# EasterEgg.net
KiCad netlist of a schematic drawn in EAGLE
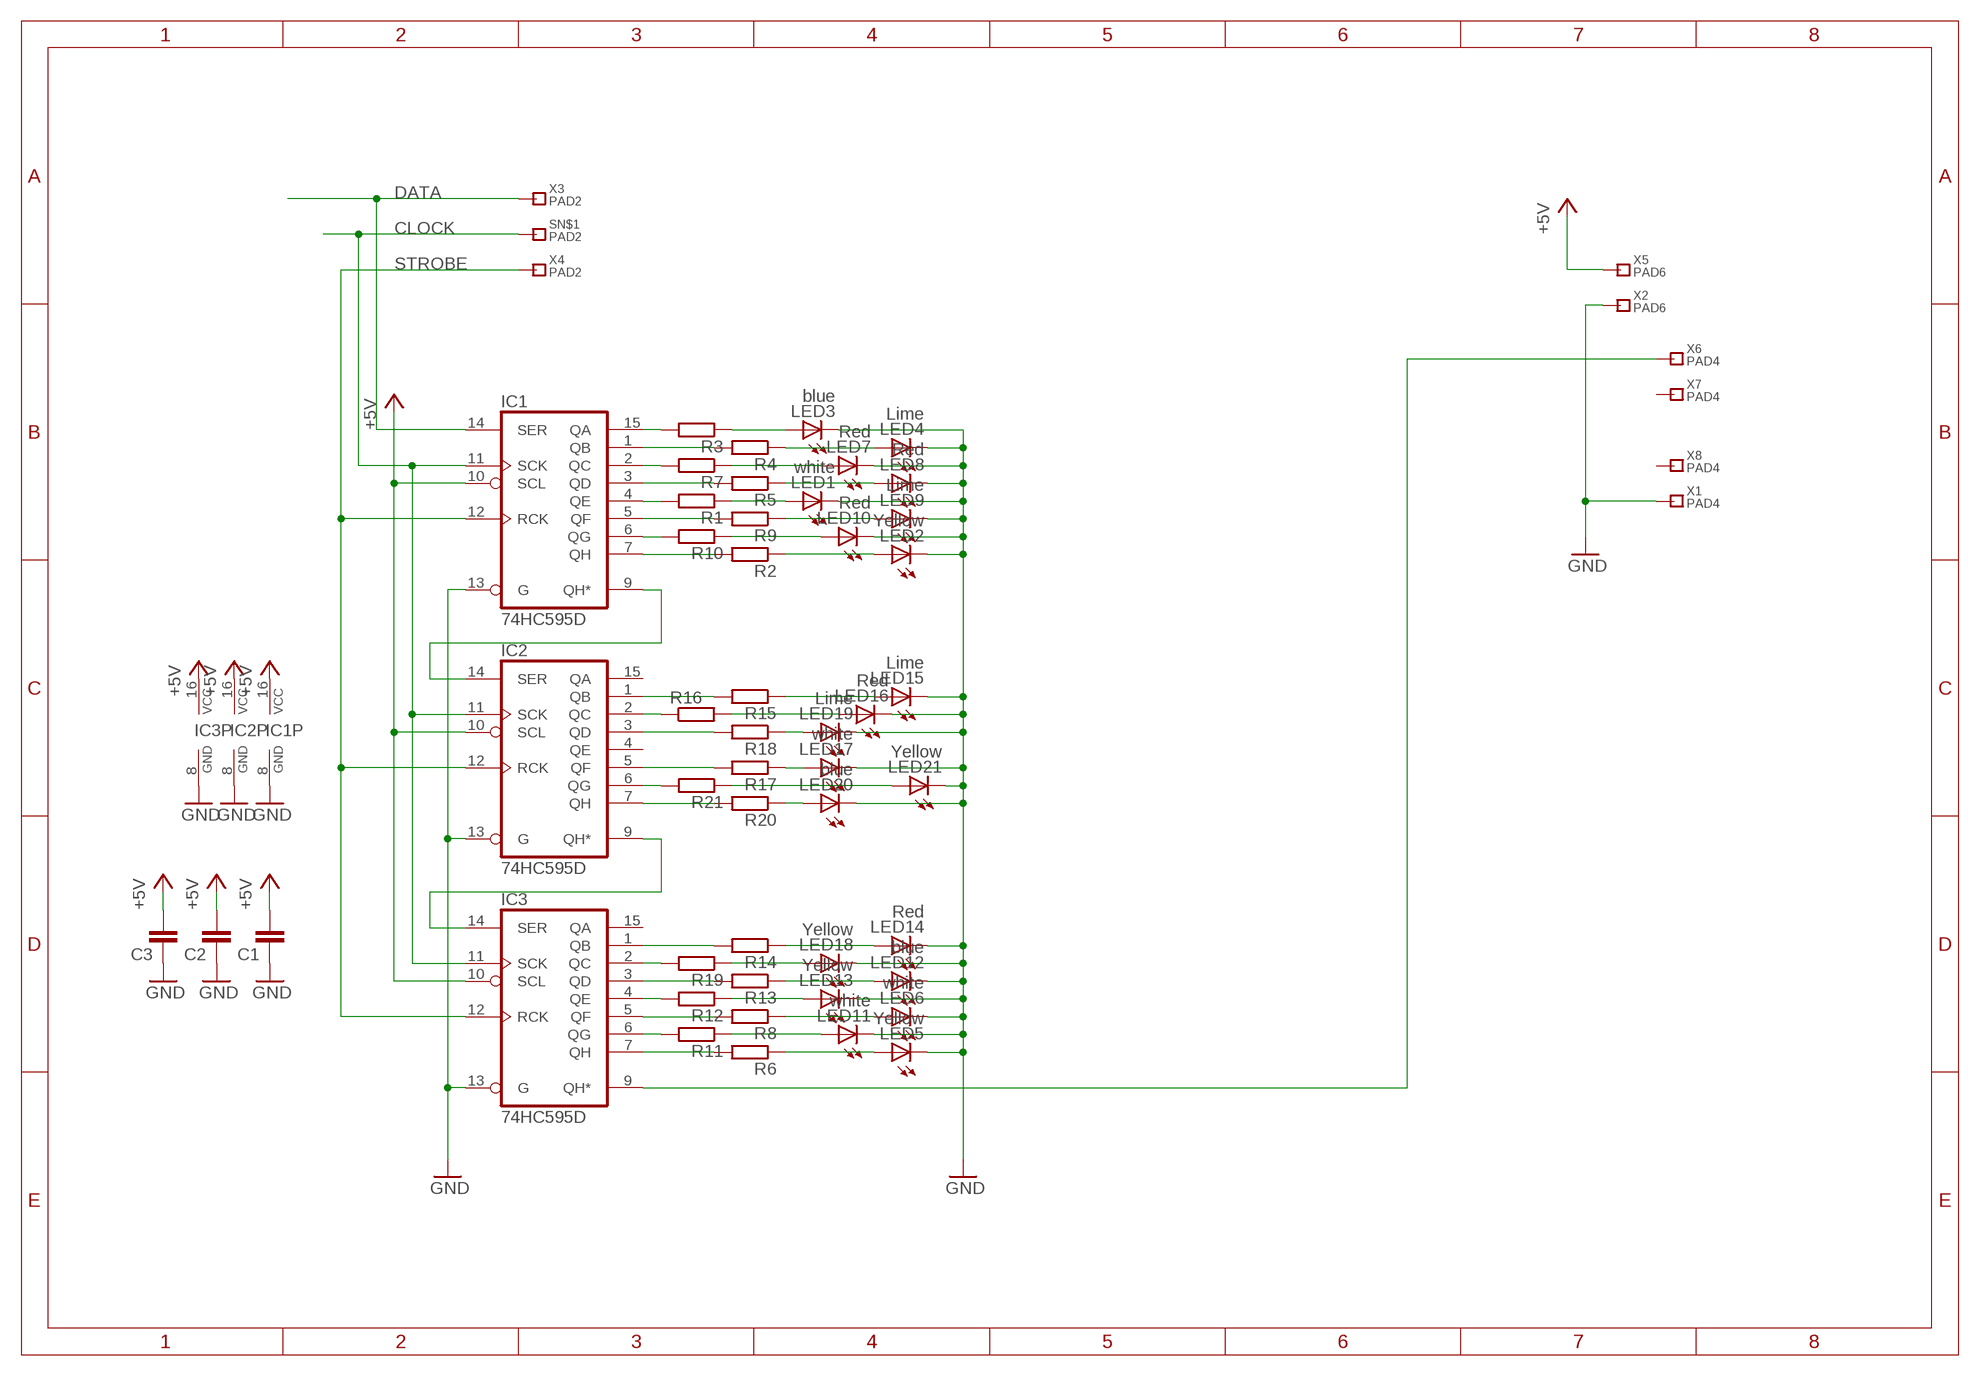
[diagram p0: schematic, sheet 1]

(export (version "E")
  (design (tool "Eeschema 10.0.6"))
  (components
    (comp (ref "C1")
      (value "C-EUC0805")
      (footprint "eagle-import:C0805")
      (libsource (lib "eagle-import") (part "C-EUC0805"))
    )
    (comp (ref "C2")
      (value "C-EUC0805")
      (footprint "eagle-import:C0805")
      (libsource (lib "eagle-import") (part "C-EUC0805"))
    )
    (comp (ref "C3")
      (value "C-EUC0805")
      (footprint "eagle-import:C0805")
      (libsource (lib "eagle-import") (part "C-EUC0805"))
    )
    (comp (ref "IC1")
      (value "74HC595D")
      (footprint "eagle-import:SO16")
      (libsource (lib "eagle-import") (part "74595DHC"))
    )
    (comp (ref "IC2")
      (value "74HC595D")
      (footprint "eagle-import:SO16")
      (libsource (lib "eagle-import") (part "74595DHC"))
    )
    (comp (ref "IC3")
      (value "74HC595D")
      (footprint "eagle-import:SO16")
      (libsource (lib "eagle-import") (part "74595DHC"))
    )
    (comp (ref "LED1")
      (value "white")
      (footprint "eagle-import:LED3MM")
      (libsource (lib "eagle-import") (part "LED3MM"))
    )
    (comp (ref "LED2")
      (value "Yellow")
      (footprint "eagle-import:LED3MM")
      (libsource (lib "eagle-import") (part "LED3MM"))
    )
    (comp (ref "LED3")
      (value "blue")
      (footprint "eagle-import:LED3MM")
      (libsource (lib "eagle-import") (part "LED3MM"))
    )
    (comp (ref "LED4")
      (value "Lime")
      (footprint "eagle-import:LED3MM")
      (libsource (lib "eagle-import") (part "LED3MM"))
    )
    (comp (ref "LED5")
      (value "Yellow")
      (footprint "eagle-import:LED3MM")
      (libsource (lib "eagle-import") (part "LED3MM"))
    )
    (comp (ref "LED6")
      (value "white")
      (footprint "eagle-import:LED3MM")
      (libsource (lib "eagle-import") (part "LED3MM"))
    )
    (comp (ref "LED7")
      (value "Red")
      (footprint "eagle-import:LED3MM")
      (libsource (lib "eagle-import") (part "LED3MM"))
    )
    (comp (ref "LED8")
      (value "Red")
      (footprint "eagle-import:LED3MM")
      (libsource (lib "eagle-import") (part "LED3MM"))
    )
    (comp (ref "LED9")
      (value "Lime")
      (footprint "eagle-import:LED3MM")
      (libsource (lib "eagle-import") (part "LED3MM"))
    )
    (comp (ref "LED10")
      (value "Red")
      (footprint "eagle-import:LED3MM")
      (libsource (lib "eagle-import") (part "LED3MM"))
    )
    (comp (ref "LED11")
      (value "white")
      (footprint "eagle-import:LED3MM")
      (libsource (lib "eagle-import") (part "LED3MM"))
    )
    (comp (ref "LED12")
      (value "blue")
      (footprint "eagle-import:LED3MM")
      (libsource (lib "eagle-import") (part "LED3MM"))
    )
    (comp (ref "LED13")
      (value "Yellow")
      (footprint "eagle-import:LED3MM")
      (libsource (lib "eagle-import") (part "LED3MM"))
    )
    (comp (ref "LED14")
      (value "Red")
      (footprint "eagle-import:LED3MM")
      (libsource (lib "eagle-import") (part "LED3MM"))
    )
    (comp (ref "LED15")
      (value "Lime")
      (footprint "eagle-import:LED3MM")
      (libsource (lib "eagle-import") (part "LED3MM"))
    )
    (comp (ref "LED16")
      (value "Red")
      (footprint "eagle-import:LED3MM")
      (libsource (lib "eagle-import") (part "LED3MM"))
    )
    (comp (ref "LED17")
      (value "white")
      (footprint "eagle-import:LED3MM")
      (libsource (lib "eagle-import") (part "LED3MM"))
    )
    (comp (ref "LED18")
      (value "Yellow")
      (footprint "eagle-import:LED3MM")
      (libsource (lib "eagle-import") (part "LED3MM"))
    )
    (comp (ref "LED19")
      (value "Lime")
      (footprint "eagle-import:LED3MM")
      (libsource (lib "eagle-import") (part "LED3MM"))
    )
    (comp (ref "LED20")
      (value "blue")
      (footprint "eagle-import:LED3MM")
      (libsource (lib "eagle-import") (part "LED3MM"))
    )
    (comp (ref "LED21")
      (value "Yellow")
      (footprint "eagle-import:LED3MM")
      (libsource (lib "eagle-import") (part "LED3MM"))
    )
    (comp (ref "R1")
      (value "R-EU_R1206")
      (footprint "eagle-import:R1206")
      (libsource (lib "eagle-import") (part "R-EU_R1206"))
    )
    (comp (ref "R2")
      (value "R-EU_R1206")
      (footprint "eagle-import:R1206")
      (libsource (lib "eagle-import") (part "R-EU_R1206"))
    )
    (comp (ref "R3")
      (value "R-EU_R1206")
      (footprint "eagle-import:R1206")
      (libsource (lib "eagle-import") (part "R-EU_R1206"))
    )
    (comp (ref "R4")
      (value "R-EU_R1206")
      (footprint "eagle-import:R1206")
      (libsource (lib "eagle-import") (part "R-EU_R1206"))
    )
    (comp (ref "R5")
      (value "R-EU_R1206")
      (footprint "eagle-import:R1206")
      (libsource (lib "eagle-import") (part "R-EU_R1206"))
    )
    (comp (ref "R6")
      (value "R-EU_R1206")
      (footprint "eagle-import:R1206")
      (libsource (lib "eagle-import") (part "R-EU_R1206"))
    )
    (comp (ref "R7")
      (value "R-EU_R1206")
      (footprint "eagle-import:R1206")
      (libsource (lib "eagle-import") (part "R-EU_R1206"))
    )
    (comp (ref "R8")
      (value "R-EU_R1206")
      (footprint "eagle-import:R1206")
      (libsource (lib "eagle-import") (part "R-EU_R1206"))
    )
    (comp (ref "R9")
      (value "R-EU_R1206")
      (footprint "eagle-import:R1206")
      (libsource (lib "eagle-import") (part "R-EU_R1206"))
    )
    (comp (ref "R10")
      (value "R-EU_R1206")
      (footprint "eagle-import:R1206")
      (libsource (lib "eagle-import") (part "R-EU_R1206"))
    )
    (comp (ref "R11")
      (value "R-EU_R1206")
      (footprint "eagle-import:R1206")
      (libsource (lib "eagle-import") (part "R-EU_R1206"))
    )
    (comp (ref "R12")
      (value "R-EU_R1206")
      (footprint "eagle-import:R1206")
      (libsource (lib "eagle-import") (part "R-EU_R1206"))
    )
    (comp (ref "R13")
      (value "R-EU_R1206")
      (footprint "eagle-import:R1206")
      (libsource (lib "eagle-import") (part "R-EU_R1206"))
    )
    (comp (ref "R14")
      (value "R-EU_R1206")
      (footprint "eagle-import:R1206")
      (libsource (lib "eagle-import") (part "R-EU_R1206"))
    )
    (comp (ref "R15")
      (value "R-EU_R1206")
      (footprint "eagle-import:R1206")
      (libsource (lib "eagle-import") (part "R-EU_R1206"))
    )
    (comp (ref "R16")
      (value "R-EU_R1206")
      (footprint "eagle-import:R1206")
      (libsource (lib "eagle-import") (part "R-EU_R1206"))
    )
    (comp (ref "R17")
      (value "R-EU_R1206")
      (footprint "eagle-import:R1206")
      (libsource (lib "eagle-import") (part "R-EU_R1206"))
    )
    (comp (ref "R18")
      (value "R-EU_R1206")
      (footprint "eagle-import:R1206")
      (libsource (lib "eagle-import") (part "R-EU_R1206"))
    )
    (comp (ref "R19")
      (value "R-EU_R1206")
      (footprint "eagle-import:R1206")
      (libsource (lib "eagle-import") (part "R-EU_R1206"))
    )
    (comp (ref "R20")
      (value "R-EU_R1206")
      (footprint "eagle-import:R1206")
      (libsource (lib "eagle-import") (part "R-EU_R1206"))
    )
    (comp (ref "R21")
      (value "R-EU_R1206")
      (footprint "eagle-import:R1206")
      (libsource (lib "eagle-import") (part "R-EU_R1206"))
    )
    (comp (ref "SN$1")
      (value "PAD2")
      (footprint "eagle-import:SMDPAD_S")
      (libsource (lib "eagle-import") (part "PAD2"))
    )
    (comp (ref "X1")
      (value "PAD4")
      (footprint "eagle-import:SMDPAD_M")
      (libsource (lib "eagle-import") (part "PAD4"))
    )
    (comp (ref "X2")
      (value "PAD6")
      (footprint "eagle-import:SMDPAD")
      (libsource (lib "eagle-import") (part "PAD6"))
    )
    (comp (ref "X3")
      (value "PAD2")
      (footprint "eagle-import:SMDPAD_S")
      (libsource (lib "eagle-import") (part "PAD2"))
    )
    (comp (ref "X4")
      (value "PAD2")
      (footprint "eagle-import:SMDPAD_S")
      (libsource (lib "eagle-import") (part "PAD2"))
    )
    (comp (ref "X5")
      (value "PAD6")
      (footprint "eagle-import:SMDPAD")
      (libsource (lib "eagle-import") (part "PAD6"))
    )
    (comp (ref "X6")
      (value "PAD4")
      (footprint "eagle-import:SMDPAD_M")
      (libsource (lib "eagle-import") (part "PAD4"))
    )
    (comp (ref "X7")
      (value "PAD4")
      (footprint "eagle-import:SMDPAD_M")
      (libsource (lib "eagle-import") (part "PAD4"))
    )
    (comp (ref "X8")
      (value "PAD4")
      (footprint "eagle-import:SMDPAD_M")
      (libsource (lib "eagle-import") (part "PAD4"))
    )
  )
  (nets
    (net (code "1") (name "+5V") (class "Default")
      (node (ref "C1") (pin "2") (pinfunction "2_2") (pintype "passive"))
      (node (ref "C2") (pin "2") (pinfunction "2_2") (pintype "passive"))
      (node (ref "C3") (pin "2") (pinfunction "2_2") (pintype "passive"))
      (node (ref "IC1") (pin "10") (pinfunction "SCL_10") (pintype "input"))
      (node (ref "IC1") (pin "16") (pinfunction "VCC_16") (pintype "power_in"))
      (node (ref "IC2") (pin "10") (pinfunction "SCL_10") (pintype "input"))
      (node (ref "IC2") (pin "16") (pinfunction "VCC_16") (pintype "power_in"))
      (node (ref "IC3") (pin "10") (pinfunction "SCL_10") (pintype "input"))
      (node (ref "IC3") (pin "16") (pinfunction "VCC_16") (pintype "power_in"))
      (node (ref "X5") (pin "P$1") (pinfunction "P$1_P$1") (pintype "bidirectional"))
    )
    (net (code "2") (name "/CLOCK") (class "Default")
      (node (ref "IC1") (pin "11") (pinfunction "SCK_11") (pintype "input"))
      (node (ref "IC2") (pin "11") (pinfunction "SCK_11") (pintype "input"))
      (node (ref "IC3") (pin "11") (pinfunction "SCK_11") (pintype "input"))
      (node (ref "SN$1") (pin "P$1") (pinfunction "P$1_P$1") (pintype "bidirectional"))
    )
    (net (code "3") (name "/DATA") (class "Default")
      (node (ref "IC1") (pin "14") (pinfunction "SER_14") (pintype "input"))
      (node (ref "X3") (pin "P$1") (pinfunction "P$1_P$1") (pintype "bidirectional"))
    )
    (net (code "4") (name "/STROBE") (class "Default")
      (node (ref "IC1") (pin "12") (pinfunction "RCK_12") (pintype "input"))
      (node (ref "IC2") (pin "12") (pinfunction "RCK_12") (pintype "input"))
      (node (ref "IC3") (pin "12") (pinfunction "RCK_12") (pintype "input"))
      (node (ref "X4") (pin "P$1") (pinfunction "P$1_P$1") (pintype "bidirectional"))
    )
    (net (code "5") (name "GND") (class "Default")
      (node (ref "C1") (pin "1") (pinfunction "1_1") (pintype "passive"))
      (node (ref "C2") (pin "1") (pinfunction "1_1") (pintype "passive"))
      (node (ref "C3") (pin "1") (pinfunction "1_1") (pintype "passive"))
      (node (ref "IC1") (pin "13") (pinfunction "G_13") (pintype "input"))
      (node (ref "IC1") (pin "8") (pinfunction "GND_8") (pintype "power_in"))
      (node (ref "IC2") (pin "13") (pinfunction "G_13") (pintype "input"))
      (node (ref "IC2") (pin "8") (pinfunction "GND_8") (pintype "power_in"))
      (node (ref "IC3") (pin "13") (pinfunction "G_13") (pintype "input"))
      (node (ref "IC3") (pin "8") (pinfunction "GND_8") (pintype "power_in"))
      (node (ref "LED1") (pin "K") (pinfunction "C_K") (pintype "passive"))
      (node (ref "LED10") (pin "K") (pinfunction "C_K") (pintype "passive"))
      (node (ref "LED11") (pin "K") (pinfunction "C_K") (pintype "passive"))
      (node (ref "LED12") (pin "K") (pinfunction "C_K") (pintype "passive"))
      (node (ref "LED13") (pin "K") (pinfunction "C_K") (pintype "passive"))
      (node (ref "LED14") (pin "K") (pinfunction "C_K") (pintype "passive"))
      (node (ref "LED15") (pin "K") (pinfunction "C_K") (pintype "passive"))
      (node (ref "LED16") (pin "K") (pinfunction "C_K") (pintype "passive"))
      (node (ref "LED17") (pin "K") (pinfunction "C_K") (pintype "passive"))
      (node (ref "LED18") (pin "K") (pinfunction "C_K") (pintype "passive"))
      (node (ref "LED19") (pin "K") (pinfunction "C_K") (pintype "passive"))
      (node (ref "LED2") (pin "K") (pinfunction "C_K") (pintype "passive"))
      (node (ref "LED20") (pin "K") (pinfunction "C_K") (pintype "passive"))
      (node (ref "LED21") (pin "K") (pinfunction "C_K") (pintype "passive"))
      (node (ref "LED3") (pin "K") (pinfunction "C_K") (pintype "passive"))
      (node (ref "LED4") (pin "K") (pinfunction "C_K") (pintype "passive"))
      (node (ref "LED5") (pin "K") (pinfunction "C_K") (pintype "passive"))
      (node (ref "LED6") (pin "K") (pinfunction "C_K") (pintype "passive"))
      (node (ref "LED7") (pin "K") (pinfunction "C_K") (pintype "passive"))
      (node (ref "LED8") (pin "K") (pinfunction "C_K") (pintype "passive"))
      (node (ref "LED9") (pin "K") (pinfunction "C_K") (pintype "passive"))
      (node (ref "X1") (pin "P$1") (pinfunction "P$1_P$1") (pintype "bidirectional"))
      (node (ref "X2") (pin "P$1") (pinfunction "P$1_P$1") (pintype "bidirectional"))
    )
    (net (code "6") (name "Net-(IC1A-QA)") (class "Default")
      (node (ref "IC1") (pin "15") (pinfunction "QA_15") (pintype "tri_state"))
      (node (ref "R3") (pin "2") (pinfunction "2_2") (pintype "passive"))
    )
    (net (code "7") (name "Net-(IC1A-QB)") (class "Default")
      (node (ref "IC1") (pin "1") (pinfunction "QB_1") (pintype "tri_state"))
      (node (ref "R4") (pin "2") (pinfunction "2_2") (pintype "passive"))
    )
    (net (code "8") (name "Net-(IC1A-QC)") (class "Default")
      (node (ref "IC1") (pin "2") (pinfunction "QC_2") (pintype "tri_state"))
      (node (ref "R7") (pin "2") (pinfunction "2_2") (pintype "passive"))
    )
    (net (code "9") (name "Net-(IC1A-QD)") (class "Default")
      (node (ref "IC1") (pin "3") (pinfunction "QD_3") (pintype "tri_state"))
      (node (ref "R5") (pin "2") (pinfunction "2_2") (pintype "passive"))
    )
    (net (code "10") (name "Net-(IC1A-QE)") (class "Default")
      (node (ref "IC1") (pin "4") (pinfunction "QE_4") (pintype "tri_state"))
      (node (ref "R1") (pin "2") (pinfunction "2_2") (pintype "passive"))
    )
    (net (code "11") (name "Net-(IC1A-QF)") (class "Default")
      (node (ref "IC1") (pin "5") (pinfunction "QF_5") (pintype "tri_state"))
      (node (ref "R9") (pin "2") (pinfunction "2_2") (pintype "passive"))
    )
    (net (code "12") (name "Net-(IC1A-QG)") (class "Default")
      (node (ref "IC1") (pin "6") (pinfunction "QG_6") (pintype "tri_state"))
      (node (ref "R10") (pin "2") (pinfunction "2_2") (pintype "passive"))
    )
    (net (code "13") (name "Net-(IC1A-QH)") (class "Default")
      (node (ref "IC1") (pin "7") (pinfunction "QH_7") (pintype "tri_state"))
      (node (ref "R2") (pin "2") (pinfunction "2_2") (pintype "passive"))
    )
    (net (code "14") (name "Net-(IC1A-QH*)") (class "Default")
      (node (ref "IC1") (pin "9") (pinfunction "QH*_9") (pintype "tri_state"))
      (node (ref "IC2") (pin "14") (pinfunction "SER_14") (pintype "input"))
    )
    (net (code "15") (name "Net-(IC2A-QB)") (class "Default")
      (node (ref "IC2") (pin "1") (pinfunction "QB_1") (pintype "tri_state"))
      (node (ref "R15") (pin "2") (pinfunction "2_2") (pintype "passive"))
    )
    (net (code "16") (name "Net-(IC2A-QC)") (class "Default")
      (node (ref "IC2") (pin "2") (pinfunction "QC_2") (pintype "tri_state"))
      (node (ref "R16") (pin "1") (pinfunction "1_1") (pintype "passive"))
    )
    (net (code "17") (name "Net-(IC2A-QD)") (class "Default")
      (node (ref "IC2") (pin "3") (pinfunction "QD_3") (pintype "tri_state"))
      (node (ref "R18") (pin "2") (pinfunction "2_2") (pintype "passive"))
    )
    (net (code "18") (name "Net-(IC2A-QF)") (class "Default")
      (node (ref "IC2") (pin "5") (pinfunction "QF_5") (pintype "tri_state"))
      (node (ref "R17") (pin "2") (pinfunction "2_2") (pintype "passive"))
    )
    (net (code "19") (name "Net-(IC2A-QG)") (class "Default")
      (node (ref "IC2") (pin "6") (pinfunction "QG_6") (pintype "tri_state"))
      (node (ref "R21") (pin "2") (pinfunction "2_2") (pintype "passive"))
    )
    (net (code "20") (name "Net-(IC2A-QH)") (class "Default")
      (node (ref "IC2") (pin "7") (pinfunction "QH_7") (pintype "tri_state"))
      (node (ref "R20") (pin "2") (pinfunction "2_2") (pintype "passive"))
    )
    (net (code "21") (name "Net-(IC2A-QH*)") (class "Default")
      (node (ref "IC2") (pin "9") (pinfunction "QH*_9") (pintype "tri_state"))
      (node (ref "IC3") (pin "14") (pinfunction "SER_14") (pintype "input"))
    )
    (net (code "22") (name "Net-(IC3A-QB)") (class "Default")
      (node (ref "IC3") (pin "1") (pinfunction "QB_1") (pintype "tri_state"))
      (node (ref "R14") (pin "2") (pinfunction "2_2") (pintype "passive"))
    )
    (net (code "23") (name "Net-(IC3A-QC)") (class "Default")
      (node (ref "IC3") (pin "2") (pinfunction "QC_2") (pintype "tri_state"))
      (node (ref "R19") (pin "2") (pinfunction "2_2") (pintype "passive"))
    )
    (net (code "24") (name "Net-(IC3A-QD)") (class "Default")
      (node (ref "IC3") (pin "3") (pinfunction "QD_3") (pintype "tri_state"))
      (node (ref "R13") (pin "2") (pinfunction "2_2") (pintype "passive"))
    )
    (net (code "25") (name "Net-(IC3A-QE)") (class "Default")
      (node (ref "IC3") (pin "4") (pinfunction "QE_4") (pintype "tri_state"))
      (node (ref "R12") (pin "2") (pinfunction "2_2") (pintype "passive"))
    )
    (net (code "26") (name "Net-(IC3A-QF)") (class "Default")
      (node (ref "IC3") (pin "5") (pinfunction "QF_5") (pintype "tri_state"))
      (node (ref "R8") (pin "2") (pinfunction "2_2") (pintype "passive"))
    )
    (net (code "27") (name "Net-(IC3A-QG)") (class "Default")
      (node (ref "IC3") (pin "6") (pinfunction "QG_6") (pintype "tri_state"))
      (node (ref "R11") (pin "2") (pinfunction "2_2") (pintype "passive"))
    )
    (net (code "28") (name "Net-(IC3A-QH)") (class "Default")
      (node (ref "IC3") (pin "7") (pinfunction "QH_7") (pintype "tri_state"))
      (node (ref "R6") (pin "2") (pinfunction "2_2") (pintype "passive"))
    )
    (net (code "29") (name "Net-(IC3A-QH*)") (class "Default")
      (node (ref "IC3") (pin "9") (pinfunction "QH*_9") (pintype "tri_state"))
      (node (ref "X6") (pin "P$1") (pinfunction "P$1_P$1") (pintype "bidirectional"))
    )
    (net (code "30") (name "Net-(LED1-PadA)") (class "Default")
      (node (ref "LED1") (pin "A") (pinfunction "A_A") (pintype "passive"))
      (node (ref "R1") (pin "1") (pinfunction "1_1") (pintype "passive"))
    )
    (net (code "31") (name "Net-(LED2-PadA)") (class "Default")
      (node (ref "LED2") (pin "A") (pinfunction "A_A") (pintype "passive"))
      (node (ref "R2") (pin "1") (pinfunction "1_1") (pintype "passive"))
    )
    (net (code "32") (name "Net-(LED3-PadA)") (class "Default")
      (node (ref "LED3") (pin "A") (pinfunction "A_A") (pintype "passive"))
      (node (ref "R3") (pin "1") (pinfunction "1_1") (pintype "passive"))
    )
    (net (code "33") (name "Net-(LED4-PadA)") (class "Default")
      (node (ref "LED4") (pin "A") (pinfunction "A_A") (pintype "passive"))
      (node (ref "R4") (pin "1") (pinfunction "1_1") (pintype "passive"))
    )
    (net (code "34") (name "Net-(LED5-PadA)") (class "Default")
      (node (ref "LED5") (pin "A") (pinfunction "A_A") (pintype "passive"))
      (node (ref "R6") (pin "1") (pinfunction "1_1") (pintype "passive"))
    )
    (net (code "35") (name "Net-(LED6-PadA)") (class "Default")
      (node (ref "LED6") (pin "A") (pinfunction "A_A") (pintype "passive"))
      (node (ref "R8") (pin "1") (pinfunction "1_1") (pintype "passive"))
    )
    (net (code "36") (name "Net-(LED7-PadA)") (class "Default")
      (node (ref "LED7") (pin "A") (pinfunction "A_A") (pintype "passive"))
      (node (ref "R7") (pin "1") (pinfunction "1_1") (pintype "passive"))
    )
    (net (code "37") (name "Net-(LED8-PadA)") (class "Default")
      (node (ref "LED8") (pin "A") (pinfunction "A_A") (pintype "passive"))
      (node (ref "R5") (pin "1") (pinfunction "1_1") (pintype "passive"))
    )
    (net (code "38") (name "Net-(LED9-PadA)") (class "Default")
      (node (ref "LED9") (pin "A") (pinfunction "A_A") (pintype "passive"))
      (node (ref "R9") (pin "1") (pinfunction "1_1") (pintype "passive"))
    )
    (net (code "39") (name "Net-(LED10-PadA)") (class "Default")
      (node (ref "LED10") (pin "A") (pinfunction "A_A") (pintype "passive"))
      (node (ref "R10") (pin "1") (pinfunction "1_1") (pintype "passive"))
    )
    (net (code "40") (name "Net-(LED11-PadA)") (class "Default")
      (node (ref "LED11") (pin "A") (pinfunction "A_A") (pintype "passive"))
      (node (ref "R11") (pin "1") (pinfunction "1_1") (pintype "passive"))
    )
    (net (code "41") (name "Net-(LED12-PadA)") (class "Default")
      (node (ref "LED12") (pin "A") (pinfunction "A_A") (pintype "passive"))
      (node (ref "R13") (pin "1") (pinfunction "1_1") (pintype "passive"))
    )
    (net (code "42") (name "Net-(LED13-PadA)") (class "Default")
      (node (ref "LED13") (pin "A") (pinfunction "A_A") (pintype "passive"))
      (node (ref "R12") (pin "1") (pinfunction "1_1") (pintype "passive"))
    )
    (net (code "43") (name "Net-(LED14-PadA)") (class "Default")
      (node (ref "LED14") (pin "A") (pinfunction "A_A") (pintype "passive"))
      (node (ref "R14") (pin "1") (pinfunction "1_1") (pintype "passive"))
    )
    (net (code "44") (name "Net-(LED15-PadA)") (class "Default")
      (node (ref "LED15") (pin "A") (pinfunction "A_A") (pintype "passive"))
      (node (ref "R15") (pin "1") (pinfunction "1_1") (pintype "passive"))
    )
    (net (code "45") (name "Net-(LED16-PadA)") (class "Default")
      (node (ref "LED16") (pin "A") (pinfunction "A_A") (pintype "passive"))
      (node (ref "R16") (pin "2") (pinfunction "2_2") (pintype "passive"))
    )
    (net (code "46") (name "Net-(LED17-PadA)") (class "Default")
      (node (ref "LED17") (pin "A") (pinfunction "A_A") (pintype "passive"))
      (node (ref "R17") (pin "1") (pinfunction "1_1") (pintype "passive"))
    )
    (net (code "47") (name "Net-(LED18-PadA)") (class "Default")
      (node (ref "LED18") (pin "A") (pinfunction "A_A") (pintype "passive"))
      (node (ref "R19") (pin "1") (pinfunction "1_1") (pintype "passive"))
    )
    (net (code "48") (name "Net-(LED19-PadA)") (class "Default")
      (node (ref "LED19") (pin "A") (pinfunction "A_A") (pintype "passive"))
      (node (ref "R18") (pin "1") (pinfunction "1_1") (pintype "passive"))
    )
    (net (code "49") (name "Net-(LED20-PadA)") (class "Default")
      (node (ref "LED20") (pin "A") (pinfunction "A_A") (pintype "passive"))
      (node (ref "R20") (pin "1") (pinfunction "1_1") (pintype "passive"))
    )
    (net (code "50") (name "Net-(LED21-PadA)") (class "Default")
      (node (ref "LED21") (pin "A") (pinfunction "A_A") (pintype "passive"))
      (node (ref "R21") (pin "1") (pinfunction "1_1") (pintype "passive"))
    )
    (net (code "51") (name "unconnected-(IC2A-QA-Pad15)") (class "Default")
      (node (ref "IC2") (pin "15") (pinfunction "QA_15") (pintype "tri_state"))
    )
    (net (code "52") (name "unconnected-(IC2A-QE-Pad4)") (class "Default")
      (node (ref "IC2") (pin "4") (pinfunction "QE_4") (pintype "tri_state"))
    )
    (net (code "53") (name "unconnected-(IC3A-QA-Pad15)") (class "Default")
      (node (ref "IC3") (pin "15") (pinfunction "QA_15") (pintype "tri_state"))
    )
    (net (code "54") (name "unconnected-(X7-PadP$1)") (class "Default")
      (node (ref "X7") (pin "P$1") (pinfunction "P$1_P$1") (pintype "bidirectional"))
    )
    (net (code "55") (name "unconnected-(X8-PadP$1)") (class "Default")
      (node (ref "X8") (pin "P$1") (pinfunction "P$1_P$1") (pintype "bidirectional"))
    )
  )
)
